# RSxxx.net
KiCad netlist of a schematic drawn in Altium Designer
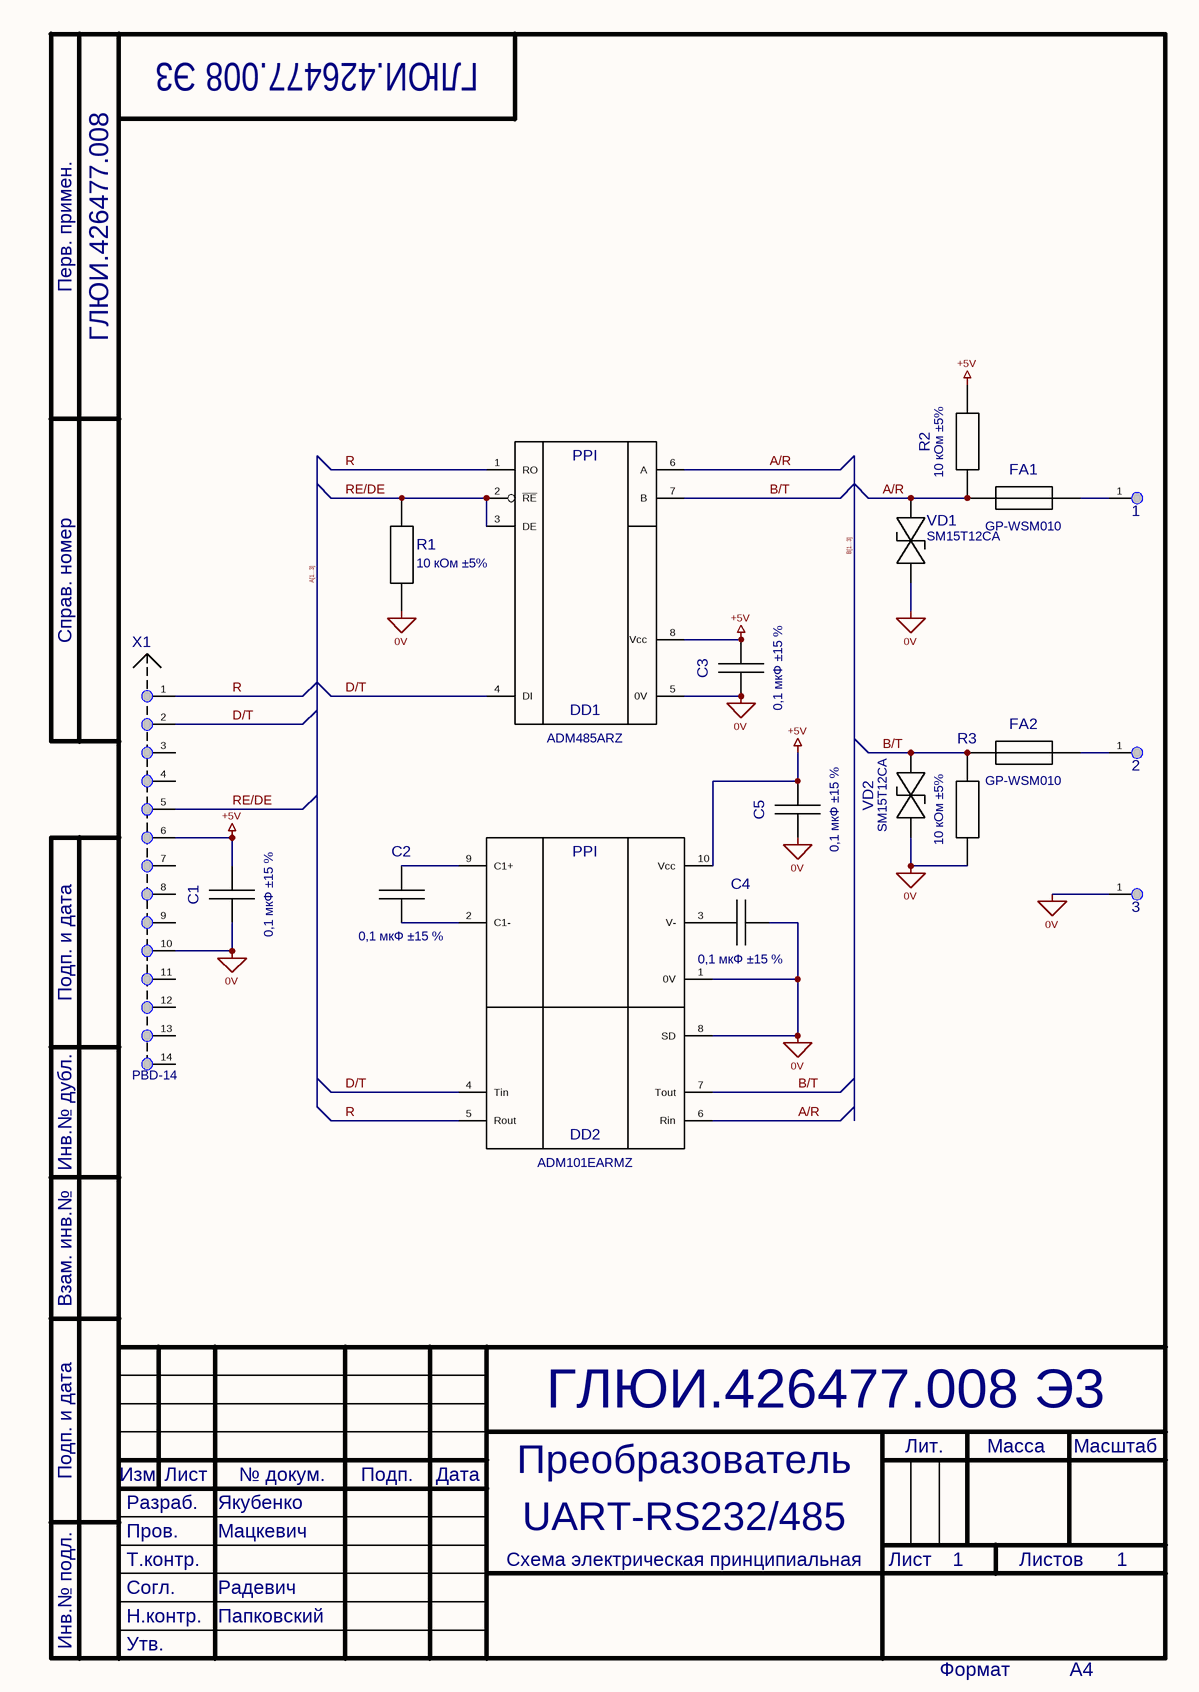
[diagram p0: RSxxx для сумматора.SchDoc]

(export (version "E")
  (design (tool "Eeschema 10.0.6"))
  (components
    (comp (ref "1")
      (value "PAD D01,8 02,5x03.0")
      (footprint "PAD D01,8 02,5x03.0")
      (libsource (lib "RSxxx дл  сумматора") (part "PAD D01,8 02,5x03.0"))
    )
    (comp (ref "2")
      (value "PAD D01,8 02,5x03.0")
      (footprint "PAD D01,8 02,5x03.0")
      (libsource (lib "RSxxx дл  сумматора") (part "PAD D01,8 02,5x03.0"))
    )
    (comp (ref "3")
      (value "PAD D01,8 02,5x03.0")
      (footprint "PAD D01,8 02,5x03.0")
      (libsource (lib "RSxxx дл  сумматора") (part "PAD D01,8 02,5x03.0"))
    )
    (comp (ref "C1")
      (value "0,1 мкФ ±15 %")
      (footprint "PAT0603")
      (description "X7R 0603-50 В-0,1 мкФ±15 %")
      (libsource (lib "RSxxx дл  сумматора") (part "X7R 0603-50 В-0,1 мкФ±15 %"))
    )
    (comp (ref "C2")
      (value "0,1 мкФ ±15 %")
      (footprint "PAT0603")
      (description "X7R 0603-50 В-0,1 мкФ±15 %")
      (libsource (lib "RSxxx дл  сумматора") (part "X7R 0603-50 В-0,1 мкФ±15 %"))
    )
    (comp (ref "C3")
      (value "0,1 мкФ ±15 %")
      (footprint "PAT0603")
      (description "X7R 0603-50 В-0,1 мкФ±15 %")
      (libsource (lib "RSxxx дл  сумматора") (part "X7R 0603-50 В-0,1 мкФ±15 %"))
    )
    (comp (ref "C4")
      (value "0,1 мкФ ±15 %")
      (footprint "PAT0603")
      (description "X7R 0603-50 В-0,1 мкФ±15 %")
      (libsource (lib "RSxxx дл  сумматора") (part "X7R 0603-50 В-0,1 мкФ±15 %"))
    )
    (comp (ref "C5")
      (value "0,1 мкФ ±15 %")
      (footprint "PAT0603")
      (description "X7R 0603-50 В-0,1 мкФ±15 %")
      (libsource (lib "RSxxx дл  сумматора") (part "X7R 0603-50 В-0,1 мкФ±15 %"))
    )
    (comp (ref "DD1")
      (value "ADM485ARZ")
      (footprint "SO-08 (150MIL)")
      (libsource (lib "RSxxx дл  сумматора") (part "ADM485ARZ"))
    )
    (comp (ref "DD2")
      (value "ADM101EARMZ")
      (footprint "SO-10 MIKRO")
      (libsource (lib "RSxxx дл  сумматора") (part "ADM101EARMZ"))
    )
    (comp (ref "FA1")
      (value "GP-WSM010")
      (footprint "GP-WMS010")
      (libsource (lib "RSxxx дл  сумматора") (part "GP-WSM010"))
    )
    (comp (ref "FA2")
      (value "GP-WSM010")
      (footprint "GP-WMS010")
      (libsource (lib "RSxxx дл  сумматора") (part "GP-WSM010"))
    )
    (comp (ref "R1")
      (value "10 кОм ±5%")
      (footprint "PAT0603")
      (description "0603 0,1 Вт-10 кОм±5 %")
      (libsource (lib "RSxxx дл  сумматора") (part "0603 0,1 Вт-10 кОм±5 %"))
    )
    (comp (ref "R2")
      (value "10 кОм ±5%")
      (footprint "PAT0603")
      (description "0603 0,1 Вт-10 кОм±5 %")
      (libsource (lib "RSxxx дл  сумматора") (part "0603 0,1 Вт-10 кОм±5 %"))
    )
    (comp (ref "R3")
      (value "10 кОм ±5%")
      (footprint "PAT0603")
      (description "0603 0,1 Вт-10 кОм±5 %")
      (libsource (lib "RSxxx дл  сумматора") (part "0603 0,1 Вт-10 кОм±5 %"))
    )
    (comp (ref "VD1")
      (value "SM15T12CA")
      (footprint "SMC")
      (libsource (lib "RSxxx дл  сумматора") (part "SM15T12CA"))
    )
    (comp (ref "VD2")
      (value "SM15T12CA")
      (footprint "SMC")
      (libsource (lib "RSxxx дл  сумматора") (part "SM15T12CA"))
    )
    (comp (ref "X1")
      (value "PBD-14")
      (footprint "PBD-14")
      (libsource (lib "RSxxx дл  сумматора") (part "PBD-14"))
    )
  )
  (nets
    (net (code "3") (name "+5V") (class "Default")
      (node (ref "C1") (pin "2") (pintype "passive"))
      (node (ref "C3") (pin "2") (pintype "passive"))
      (node (ref "C5") (pin "2") (pintype "passive"))
      (node (ref "DD1") (pin "8") (pinfunction "Vcc_8") (pintype "passive"))
      (node (ref "DD2") (pin "10") (pinfunction "Vcc_10") (pintype "passive"))
      (node (ref "R2") (pin "2") (pintype "passive"))
      (node (ref "X1") (pin "6") (pintype "passive"))
    )
    (net (code "4") (name "/A{slash}R") (class "Default")
      (node (ref "DD1") (pin "6") (pinfunction "A_6") (pintype "passive"))
      (node (ref "DD2") (pin "6") (pinfunction "Rin_6") (pintype "passive"))
      (node (ref "FA1") (pin "1") (pintype "passive"))
      (node (ref "R2") (pin "1") (pintype "passive"))
      (node (ref "VD1") (pin "2") (pintype "passive"))
    )
    (net (code "5") (name "/B{slash}T") (class "Default")
      (node (ref "DD1") (pin "7") (pinfunction "B_7") (pintype "passive"))
      (node (ref "DD2") (pin "7") (pinfunction "Tout_7") (pintype "passive"))
      (node (ref "FA2") (pin "1") (pintype "passive"))
      (node (ref "R3") (pin "2") (pintype "passive"))
      (node (ref "VD2") (pin "2") (pintype "passive"))
    )
    (net (code "6") (name "/D{slash}T") (class "Default")
      (node (ref "DD1") (pin "4") (pinfunction "DI_4") (pintype "passive"))
      (node (ref "DD2") (pin "4") (pinfunction "Tin_4") (pintype "passive"))
      (node (ref "X1") (pin "2") (pintype "passive"))
    )
    (net (code "7") (name "/R") (class "Default")
      (node (ref "DD1") (pin "1") (pinfunction "RO_1") (pintype "passive"))
      (node (ref "DD2") (pin "5") (pinfunction "Rout_5") (pintype "passive"))
      (node (ref "X1") (pin "1") (pintype "passive"))
    )
    (net (code "8") (name "/RE{slash}DE") (class "Default")
      (node (ref "DD1") (pin "2") (pinfunction "~{RE}_2") (pintype "passive"))
      (node (ref "DD1") (pin "3") (pinfunction "DE_3") (pintype "passive"))
      (node (ref "R1") (pin "2") (pintype "passive"))
      (node (ref "X1") (pin "5") (pintype "passive"))
    )
    (net (code "11") (name "0V") (class "Default")
      (node (ref "3") (pin "1") (pintype "passive"))
      (node (ref "C1") (pin "1") (pintype "passive"))
      (node (ref "C3") (pin "1") (pintype "passive"))
      (node (ref "C4") (pin "1") (pintype "passive"))
      (node (ref "C5") (pin "1") (pintype "passive"))
      (node (ref "DD1") (pin "5") (pinfunction "0V_5") (pintype "passive"))
      (node (ref "DD2") (pin "1") (pinfunction "0V_1") (pintype "passive"))
      (node (ref "DD2") (pin "8") (pinfunction "SD_8") (pintype "passive"))
      (node (ref "R1") (pin "1") (pintype "passive"))
      (node (ref "R3") (pin "1") (pintype "passive"))
      (node (ref "VD1") (pin "1") (pintype "passive"))
      (node (ref "VD2") (pin "1") (pintype "passive"))
      (node (ref "X1") (pin "10") (pintype "passive"))
    )
    (net (code "12") (name "Net-(1-Pad1)") (class "Default")
      (node (ref "1") (pin "1") (pintype "passive"))
      (node (ref "FA1") (pin "2") (pintype "passive"))
    )
    (net (code "13") (name "Net-(2-Pad1)") (class "Default")
      (node (ref "2") (pin "1") (pintype "passive"))
      (node (ref "FA2") (pin "2") (pintype "passive"))
    )
    (net (code "14") (name "Net-(DD2-C1+)") (class "Default")
      (node (ref "C2") (pin "2") (pintype "passive"))
      (node (ref "DD2") (pin "9") (pinfunction "C1+_9") (pintype "passive"))
    )
    (net (code "15") (name "Net-(DD2-C1-)") (class "Default")
      (node (ref "C2") (pin "1") (pintype "passive"))
      (node (ref "DD2") (pin "2") (pinfunction "C1-_2") (pintype "passive"))
    )
    (net (code "16") (name "Net-(DD2-V-)") (class "Default")
      (node (ref "C4") (pin "2") (pintype "passive"))
      (node (ref "DD2") (pin "3") (pinfunction "V-_3") (pintype "passive"))
    )
    (net (code "17") (name "unconnected-(X1-Pad3)") (class "Default")
      (node (ref "X1") (pin "3") (pintype "passive"))
    )
    (net (code "18") (name "unconnected-(X1-Pad4)") (class "Default")
      (node (ref "X1") (pin "4") (pintype "passive"))
    )
    (net (code "19") (name "unconnected-(X1-Pad7)") (class "Default")
      (node (ref "X1") (pin "7") (pintype "passive"))
    )
    (net (code "20") (name "unconnected-(X1-Pad8)") (class "Default")
      (node (ref "X1") (pin "8") (pintype "passive"))
    )
    (net (code "21") (name "unconnected-(X1-Pad9)") (class "Default")
      (node (ref "X1") (pin "9") (pintype "passive"))
    )
    (net (code "22") (name "unconnected-(X1-Pad11)") (class "Default")
      (node (ref "X1") (pin "11") (pintype "passive"))
    )
    (net (code "23") (name "unconnected-(X1-Pad12)") (class "Default")
      (node (ref "X1") (pin "12") (pintype "passive"))
    )
    (net (code "24") (name "unconnected-(X1-Pad13)") (class "Default")
      (node (ref "X1") (pin "13") (pintype "passive"))
    )
    (net (code "25") (name "unconnected-(X1-Pad14)") (class "Default")
      (node (ref "X1") (pin "14") (pintype "passive"))
    )
  )
)
